# Vibrator_driver-FSR.net
KiCad netlist of a schematic drawn in EAGLE
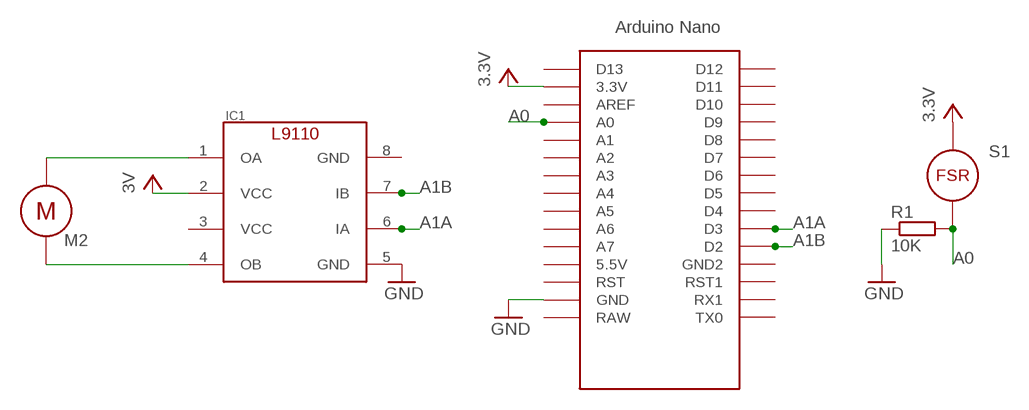
[diagram p0: schematic, sheet 1]

(export (version "E")
  (design (tool "Eeschema 10.0.6"))
  (components
    (comp (ref "IC1")
      (value "L9110")
      (footprint "eagle-import:SO8P")
      (libsource (lib "eagle-import") (part "L9110"))
    )
    (comp (ref "M2")
      (value "308-100")
      (footprint "eagle-import:308-100")
      (libsource (lib "eagle-import") (part "motor_308-100"))
    )
    (comp (ref "R1")
      (value "10K")
      (footprint "eagle-import:0204_7")
      (libsource (lib "eagle-import") (part "R-EU_0204/7"))
    )
    (comp (ref "S1")
      (value "308-100")
      (footprint "eagle-import:308-100")
      (libsource (lib "eagle-import") (part "308-100"))
    )
    (comp (ref "U$1")
      (value "NANO")
      (footprint "eagle-import:NANO")
      (libsource (lib "eagle-import") (part "NANO"))
    )
  )
  (nets
    (net (code "1") (name "/A0") (class "Default")
      (node (ref "R1") (pin "2") (pinfunction "2_2") (pintype "passive"))
      (node (ref "S1") (pin "NEG") (pinfunction "NEG_NEG") (pintype "bidirectional"))
      (node (ref "U$1") (pin "A0") (pinfunction "A0_A0") (pintype "bidirectional"))
    )
    (net (code "2") (name "/A1A") (class "Default")
      (node (ref "IC1") (pin "6") (pinfunction "IA_6") (pintype "bidirectional"))
      (node (ref "U$1") (pin "D3") (pinfunction "D3_D3") (pintype "bidirectional"))
    )
    (net (code "3") (name "/A1B") (class "Default")
      (node (ref "IC1") (pin "7") (pinfunction "IB_7") (pintype "bidirectional"))
      (node (ref "U$1") (pin "D2") (pinfunction "D2_D2") (pintype "bidirectional"))
    )
    (net (code "4") (name "3.3V") (class "Default")
      (node (ref "IC1") (pin "2") (pinfunction "VCC_2") (pintype "bidirectional"))
      (node (ref "S1") (pin "POS") (pinfunction "POS_POS") (pintype "bidirectional"))
      (node (ref "U$1") (pin "3.3V") (pinfunction "3.3V_3.3V") (pintype "bidirectional"))
    )
    (net (code "5") (name "GND") (class "Default")
      (node (ref "IC1") (pin "5") (pinfunction "GND_5") (pintype "bidirectional"))
      (node (ref "R1") (pin "1") (pinfunction "1_1") (pintype "passive"))
      (node (ref "U$1") (pin "GND") (pinfunction "GND_GND") (pintype "bidirectional"))
    )
    (net (code "6") (name "Net-(IC1-OA)") (class "Default")
      (node (ref "IC1") (pin "1") (pinfunction "OA_1") (pintype "bidirectional"))
      (node (ref "M2") (pin "POS") (pinfunction "POS_POS") (pintype "bidirectional"))
    )
    (net (code "7") (name "Net-(IC1-OB)") (class "Default")
      (node (ref "IC1") (pin "4") (pinfunction "OB_4") (pintype "bidirectional"))
      (node (ref "M2") (pin "NEG") (pinfunction "NEG_NEG") (pintype "bidirectional"))
    )
    (net (code "8") (name "unconnected-(IC1-GND-Pad8)") (class "Default")
      (node (ref "IC1") (pin "8") (pinfunction "GND_8") (pintype "bidirectional"))
    )
    (net (code "9") (name "unconnected-(IC1-VCC-Pad3)") (class "Default")
      (node (ref "IC1") (pin "3") (pinfunction "VCC_3") (pintype "bidirectional"))
    )
    (net (code "10") (name "unconnected-(U$1-5.5V-Pad5V)") (class "Default")
      (node (ref "U$1") (pin "5V") (pinfunction "5.5V_5V") (pintype "bidirectional"))
    )
    (net (code "11") (name "unconnected-(U$1-GND2-PadGND1)") (class "Default")
      (node (ref "U$1") (pin "GND1") (pinfunction "GND2_GND1") (pintype "bidirectional"))
    )
    (net (code "12") (name "unconnected-(U$1-PadA1)") (class "Default")
      (node (ref "U$1") (pin "A1") (pinfunction "A1_A1") (pintype "bidirectional"))
    )
    (net (code "13") (name "unconnected-(U$1-PadA2)") (class "Default")
      (node (ref "U$1") (pin "A2") (pinfunction "A2_A2") (pintype "bidirectional"))
    )
    (net (code "14") (name "unconnected-(U$1-PadA3)") (class "Default")
      (node (ref "U$1") (pin "A3") (pinfunction "A3_A3") (pintype "bidirectional"))
    )
    (net (code "15") (name "unconnected-(U$1-PadA4)") (class "Default")
      (node (ref "U$1") (pin "A4") (pinfunction "A4_A4") (pintype "bidirectional"))
    )
    (net (code "16") (name "unconnected-(U$1-PadA5)") (class "Default")
      (node (ref "U$1") (pin "A5") (pinfunction "A5_A5") (pintype "bidirectional"))
    )
    (net (code "17") (name "unconnected-(U$1-PadA6)") (class "Default")
      (node (ref "U$1") (pin "A6") (pinfunction "A6_A6") (pintype "bidirectional"))
    )
    (net (code "18") (name "unconnected-(U$1-PadA7)") (class "Default")
      (node (ref "U$1") (pin "A7") (pinfunction "A7_A7") (pintype "bidirectional"))
    )
    (net (code "19") (name "unconnected-(U$1-PadAREF)") (class "Default")
      (node (ref "U$1") (pin "AREF") (pinfunction "AREF_AREF") (pintype "bidirectional"))
    )
    (net (code "20") (name "unconnected-(U$1-PadD4)") (class "Default")
      (node (ref "U$1") (pin "D4") (pinfunction "D4_D4") (pintype "bidirectional"))
    )
    (net (code "21") (name "unconnected-(U$1-PadD5)") (class "Default")
      (node (ref "U$1") (pin "D5") (pinfunction "D5_D5") (pintype "bidirectional"))
    )
    (net (code "22") (name "unconnected-(U$1-PadD6)") (class "Default")
      (node (ref "U$1") (pin "D6") (pinfunction "D6_D6") (pintype "bidirectional"))
    )
    (net (code "23") (name "unconnected-(U$1-PadD7)") (class "Default")
      (node (ref "U$1") (pin "D7") (pinfunction "D7_D7") (pintype "bidirectional"))
    )
    (net (code "24") (name "unconnected-(U$1-PadD8)") (class "Default")
      (node (ref "U$1") (pin "D8") (pinfunction "D8_D8") (pintype "bidirectional"))
    )
    (net (code "25") (name "unconnected-(U$1-PadD9)") (class "Default")
      (node (ref "U$1") (pin "D9") (pinfunction "D9_D9") (pintype "bidirectional"))
    )
    (net (code "26") (name "unconnected-(U$1-PadD10)") (class "Default")
      (node (ref "U$1") (pin "D10") (pinfunction "D10_D10") (pintype "bidirectional"))
    )
    (net (code "27") (name "unconnected-(U$1-PadD11)") (class "Default")
      (node (ref "U$1") (pin "D11") (pinfunction "D11_D11") (pintype "bidirectional"))
    )
    (net (code "28") (name "unconnected-(U$1-PadD12)") (class "Default")
      (node (ref "U$1") (pin "D12") (pinfunction "D12_D12") (pintype "bidirectional"))
    )
    (net (code "29") (name "unconnected-(U$1-PadD13)") (class "Default")
      (node (ref "U$1") (pin "D13") (pinfunction "D13_D13") (pintype "bidirectional"))
    )
    (net (code "30") (name "unconnected-(U$1-PadICSP1)") (class "Default")
      (node (ref "U$1") (pin "ICSP1") (pinfunction "ICSP1_ICSP1") (pintype "bidirectional"))
    )
    (net (code "31") (name "unconnected-(U$1-PadICSP2)") (class "Default")
      (node (ref "U$1") (pin "ICSP2") (pinfunction "ICSP2_ICSP2") (pintype "bidirectional"))
    )
    (net (code "32") (name "unconnected-(U$1-PadICSP3)") (class "Default")
      (node (ref "U$1") (pin "ICSP3") (pinfunction "ICSP3_ICSP3") (pintype "bidirectional"))
    )
    (net (code "33") (name "unconnected-(U$1-PadICSP4)") (class "Default")
      (node (ref "U$1") (pin "ICSP4") (pinfunction "ICSP4_ICSP4") (pintype "bidirectional"))
    )
    (net (code "34") (name "unconnected-(U$1-PadICSP5)") (class "Default")
      (node (ref "U$1") (pin "ICSP5") (pinfunction "ICSP5_ICSP5") (pintype "bidirectional"))
    )
    (net (code "35") (name "unconnected-(U$1-PadICSP6)") (class "Default")
      (node (ref "U$1") (pin "ICSP6") (pinfunction "ICSP6_ICSP6") (pintype "bidirectional"))
    )
    (net (code "36") (name "unconnected-(U$1-PadRAW)") (class "Default")
      (node (ref "U$1") (pin "RAW") (pinfunction "RAW_RAW") (pintype "bidirectional"))
    )
    (net (code "37") (name "unconnected-(U$1-PadRST)") (class "Default")
      (node (ref "U$1") (pin "RST") (pinfunction "RST_RST") (pintype "bidirectional"))
    )
    (net (code "38") (name "unconnected-(U$1-PadRST1)") (class "Default")
      (node (ref "U$1") (pin "RST1") (pinfunction "RST1_RST1") (pintype "bidirectional"))
    )
    (net (code "39") (name "unconnected-(U$1-PadRX1)") (class "Default")
      (node (ref "U$1") (pin "RX1") (pinfunction "RX1_RX1") (pintype "bidirectional"))
    )
    (net (code "40") (name "unconnected-(U$1-PadTX0)") (class "Default")
      (node (ref "U$1") (pin "TX0") (pinfunction "TX0_TX0") (pintype "bidirectional"))
    )
  )
)
